# Smartphone-HT.net
KiCad netlist of a schematic drawn in Altium Designer
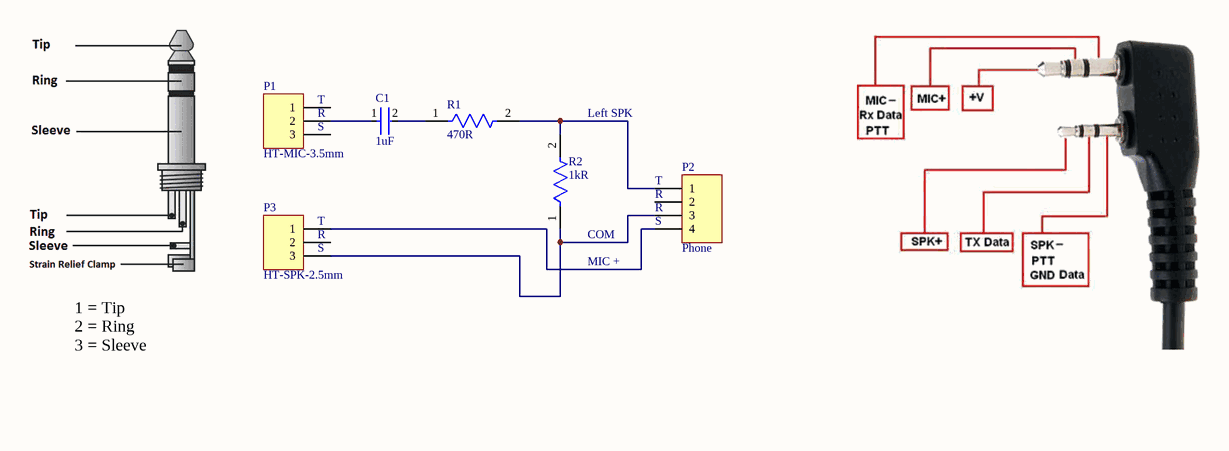
[diagram p0: Smartphone-HT.SchDoc]

(export (version "E")
  (design (tool "Eeschema 10.0.6"))
  (components
    (comp (ref "C1")
      (value "1uF")
      (footprint "FP-0603-L_1_6_0_15-W_0_8-IPC_C")
      (description "Ceramic Capacitor General Use 1uF ±10% 50V X7R 0603")
      (fields (field (name "TOLERANCE") "10%"))
      (libsource (lib "Altium Content Vault") (part "11868f565c42a9108669ba33697ecf6"))
    )
    (comp (ref "P1")
      (value "HT-MIC-3.5mm")
      (footprint "HDR1X3")
      (description "Header, 3-Pin")
      (fields (field (name "PUBLISHER") "Altium Limited"))
      (libsource (lib "Miscellaneous Connectors") (part "Header 3"))
    )
    (comp (ref "P2")
      (value "Phone")
      (footprint "HDR1X4")
      (description "Header, 4-Pin")
      (fields (field (name "PUBLISHER") "Altium Limited"))
      (libsource (lib "Miscellaneous Connectors") (part "Header 4"))
    )
    (comp (ref "P3")
      (value "HT-SPK-2.5mm")
      (footprint "HDR1X3")
      (description "Header, 3-Pin")
      (fields (field (name "PUBLISHER") "Altium Limited"))
      (libsource (lib "Miscellaneous Connectors") (part "Header 3"))
    )
    (comp (ref "R1")
      (value "470R")
      (footprint "FP-CRCW0603-e3-MFG")
      (description "RES Thick Film, 470Ω, 1%, 0.1W, 100ppm/°C, 0603")
      (fields (field (name "TOLERANCE") "1%"))
      (libsource (lib "Altium Content Vault") (part "1029c3af85768c4190bb7ad29bc67b5"))
    )
    (comp (ref "R2")
      (value "1kR")
      (footprint "FP-ERA3A-IPC_C")
      (description "RES SMD 1K OHM 0.1% 1/10W 0603")
      (fields (field (name "TOLERANCE") "0.1%"))
      (libsource (lib "Altium Content Vault") (part "1029c3af85768c4190bb7ad29bc67b5"))
    )
  )
  (nets
    (net (code "1") (name "Net-(C1-Pad1)") (class "Default")
      (node (ref "C1") (pin "1") (pinfunction "1_1") (pintype "passive"))
      (node (ref "P1") (pin "2") (pinfunction "2_2") (pintype "passive"))
    )
    (net (code "2") (name "Net-(C1-Pad2)") (class "Default")
      (node (ref "C1") (pin "2") (pinfunction "2_2") (pintype "passive"))
      (node (ref "R1") (pin "1") (pinfunction "1_1") (pintype "passive"))
    )
    (net (code "3") (name "Net-(P2-Pad1)") (class "Default")
      (node (ref "P2") (pin "1") (pinfunction "1_1") (pintype "passive"))
      (node (ref "R1") (pin "2") (pinfunction "2_2") (pintype "passive"))
      (node (ref "R2") (pin "2") (pinfunction "2_2") (pintype "passive"))
    )
    (net (code "4") (name "Net-(P2-Pad3)") (class "Default")
      (node (ref "P2") (pin "3") (pinfunction "3_3") (pintype "passive"))
      (node (ref "P3") (pin "3") (pinfunction "3_3") (pintype "passive"))
      (node (ref "R2") (pin "1") (pinfunction "1_1") (pintype "passive"))
    )
    (net (code "5") (name "Net-(P2-Pad4)") (class "Default")
      (node (ref "P2") (pin "4") (pinfunction "4_4") (pintype "passive"))
      (node (ref "P3") (pin "1") (pinfunction "1_1") (pintype "passive"))
    )
    (net (code "6") (name "unconnected-(P1-Pad1)") (class "Default")
      (node (ref "P1") (pin "1") (pinfunction "1_1") (pintype "passive"))
    )
    (net (code "7") (name "unconnected-(P1-Pad3)") (class "Default")
      (node (ref "P1") (pin "3") (pinfunction "3_3") (pintype "passive"))
    )
    (net (code "8") (name "unconnected-(P2-Pad2)") (class "Default")
      (node (ref "P2") (pin "2") (pinfunction "2_2") (pintype "passive"))
    )
    (net (code "9") (name "unconnected-(P3-Pad2)") (class "Default")
      (node (ref "P3") (pin "2") (pinfunction "2_2") (pintype "passive"))
    )
  )
)
